# LSM9DS0_Breakout_Board.net
KiCad netlist of a schematic drawn in EAGLE
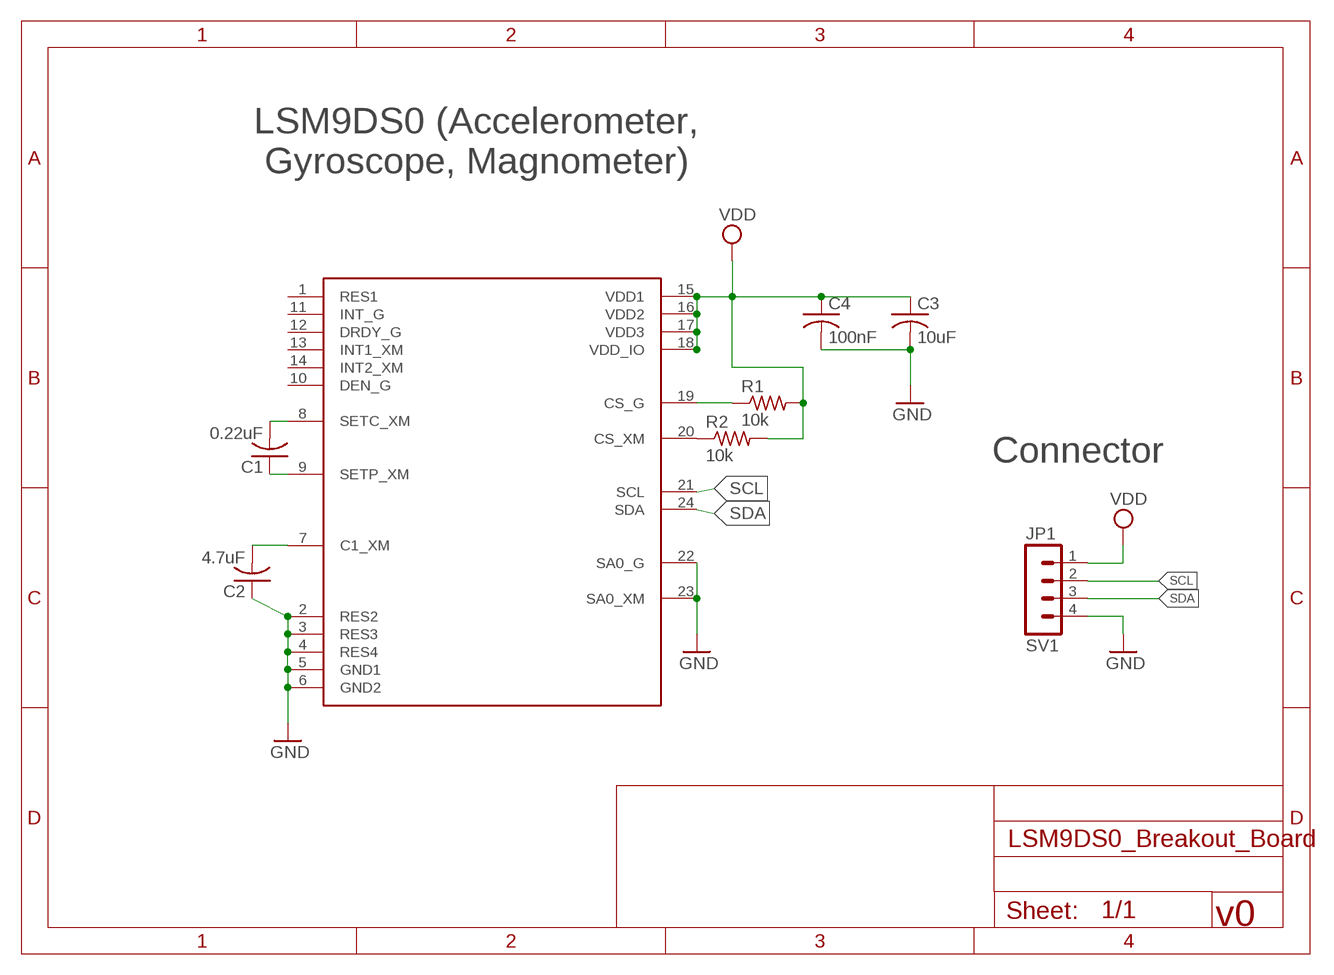
[diagram p0: schematic, sheet 1]

(export (version "E")
  (design (tool "Eeschema 10.0.6"))
  (components
    (comp (ref "C1")
      (value "0.22uF")
      (footprint "eagle-import:C0805")
      (libsource (lib "eagle-import") (part "C-USC0805"))
    )
    (comp (ref "C2")
      (value "4.7uF")
      (footprint "eagle-import:C0805")
      (libsource (lib "eagle-import") (part "C-USC0805"))
    )
    (comp (ref "C3")
      (value "10uF")
      (footprint "eagle-import:C0805")
      (libsource (lib "eagle-import") (part "C-USC0805"))
    )
    (comp (ref "C4")
      (value "100nF")
      (footprint "eagle-import:C0805")
      (libsource (lib "eagle-import") (part "C-USC0805"))
    )
    (comp (ref "R1")
      (value "10k")
      (footprint "eagle-import:R0805")
      (libsource (lib "eagle-import") (part "R-US_R0805"))
    )
    (comp (ref "R2")
      (value "10k")
      (footprint "eagle-import:R0805")
      (libsource (lib "eagle-import") (part "R-US_R0805"))
    )
    (comp (ref "SV1")
      (value "JP1")
      (footprint "eagle-import:MA04-1")
      (libsource (lib "eagle-import") (part "MA04-1"))
    )
    (comp (ref "U1")
      (value "LSM9DS0")
      (footprint "eagle-import:LGA-24")
      (libsource (lib "eagle-import") (part "LSM9DS0"))
    )
  )
  (nets
    (net (code "1") (name "GND") (class "Default")
      (node (ref "C2") (pin "1") (pinfunction "1_1") (pintype "passive"))
      (node (ref "C3") (pin "2") (pinfunction "2_2") (pintype "passive"))
      (node (ref "C4") (pin "2") (pinfunction "2_2") (pintype "passive"))
      (node (ref "SV1") (pin "4") (pinfunction "4_4") (pintype "passive"))
      (node (ref "U1") (pin "2") (pinfunction "RES2_2") (pintype "bidirectional"))
      (node (ref "U1") (pin "22") (pinfunction "SA0_G_22") (pintype "bidirectional"))
      (node (ref "U1") (pin "23") (pinfunction "SA0_XM_23") (pintype "bidirectional"))
      (node (ref "U1") (pin "3") (pinfunction "RES3_3") (pintype "bidirectional"))
      (node (ref "U1") (pin "4") (pinfunction "RES4_4") (pintype "bidirectional"))
      (node (ref "U1") (pin "5") (pinfunction "GND1_5") (pintype "bidirectional"))
      (node (ref "U1") (pin "6") (pinfunction "GND2_6") (pintype "bidirectional"))
    )
    (net (code "2") (name "Net-(U1-C1_XM)") (class "Default")
      (node (ref "C2") (pin "2") (pinfunction "2_2") (pintype "passive"))
      (node (ref "U1") (pin "7") (pinfunction "C1_XM_7") (pintype "bidirectional"))
    )
    (net (code "3") (name "Net-(U1-CS_G)") (class "Default")
      (node (ref "R1") (pin "1") (pinfunction "1_1") (pintype "passive"))
      (node (ref "U1") (pin "19") (pinfunction "CS_G_19") (pintype "bidirectional"))
    )
    (net (code "4") (name "Net-(U1-CS_XM)") (class "Default")
      (node (ref "R2") (pin "1") (pinfunction "1_1") (pintype "passive"))
      (node (ref "U1") (pin "20") (pinfunction "CS_XM_20") (pintype "bidirectional"))
    )
    (net (code "5") (name "Net-(U1-SETC_XM)") (class "Default")
      (node (ref "C1") (pin "2") (pinfunction "2_2") (pintype "passive"))
      (node (ref "U1") (pin "8") (pinfunction "SETC_XM_8") (pintype "bidirectional"))
    )
    (net (code "6") (name "Net-(U1-SETP_XM)") (class "Default")
      (node (ref "C1") (pin "1") (pinfunction "1_1") (pintype "passive"))
      (node (ref "U1") (pin "9") (pinfunction "SETP_XM_9") (pintype "bidirectional"))
    )
    (net (code "7") (name "SCL") (class "Default")
      (node (ref "SV1") (pin "2") (pinfunction "2_2") (pintype "passive"))
      (node (ref "U1") (pin "21") (pinfunction "SCL_21") (pintype "bidirectional"))
    )
    (net (code "8") (name "SDA") (class "Default")
      (node (ref "SV1") (pin "3") (pinfunction "3_3") (pintype "passive"))
      (node (ref "U1") (pin "24") (pinfunction "SDA_24") (pintype "bidirectional"))
    )
    (net (code "9") (name "VDD") (class "Default")
      (node (ref "C3") (pin "1") (pinfunction "1_1") (pintype "passive"))
      (node (ref "C4") (pin "1") (pinfunction "1_1") (pintype "passive"))
      (node (ref "R1") (pin "2") (pinfunction "2_2") (pintype "passive"))
      (node (ref "R2") (pin "2") (pinfunction "2_2") (pintype "passive"))
      (node (ref "SV1") (pin "1") (pinfunction "1_1") (pintype "passive"))
      (node (ref "U1") (pin "15") (pinfunction "VDD1_15") (pintype "bidirectional"))
      (node (ref "U1") (pin "16") (pinfunction "VDD2_16") (pintype "bidirectional"))
      (node (ref "U1") (pin "17") (pinfunction "VDD3_17") (pintype "bidirectional"))
      (node (ref "U1") (pin "18") (pinfunction "VDD_IO_18") (pintype "bidirectional"))
    )
    (net (code "10") (name "unconnected-(U1-DEN_G-Pad10)") (class "Default")
      (node (ref "U1") (pin "10") (pinfunction "DEN_G_10") (pintype "bidirectional"))
    )
    (net (code "11") (name "unconnected-(U1-DRDY_G-Pad12)") (class "Default")
      (node (ref "U1") (pin "12") (pinfunction "DRDY_G_12") (pintype "bidirectional"))
    )
    (net (code "12") (name "unconnected-(U1-INT1_XM-Pad13)") (class "Default")
      (node (ref "U1") (pin "13") (pinfunction "INT1_XM_13") (pintype "bidirectional"))
    )
    (net (code "13") (name "unconnected-(U1-INT2_XM-Pad14)") (class "Default")
      (node (ref "U1") (pin "14") (pinfunction "INT2_XM_14") (pintype "bidirectional"))
    )
    (net (code "14") (name "unconnected-(U1-INT_G-Pad11)") (class "Default")
      (node (ref "U1") (pin "11") (pinfunction "INT_G_11") (pintype "bidirectional"))
    )
    (net (code "15") (name "unconnected-(U1-RES1-Pad1)") (class "Default")
      (node (ref "U1") (pin "1") (pinfunction "RES1_1") (pintype "bidirectional"))
    )
  )
)
